# MCU_STM32_L496ZGT6.net
KiCad netlist of a schematic drawn in Altium Designer
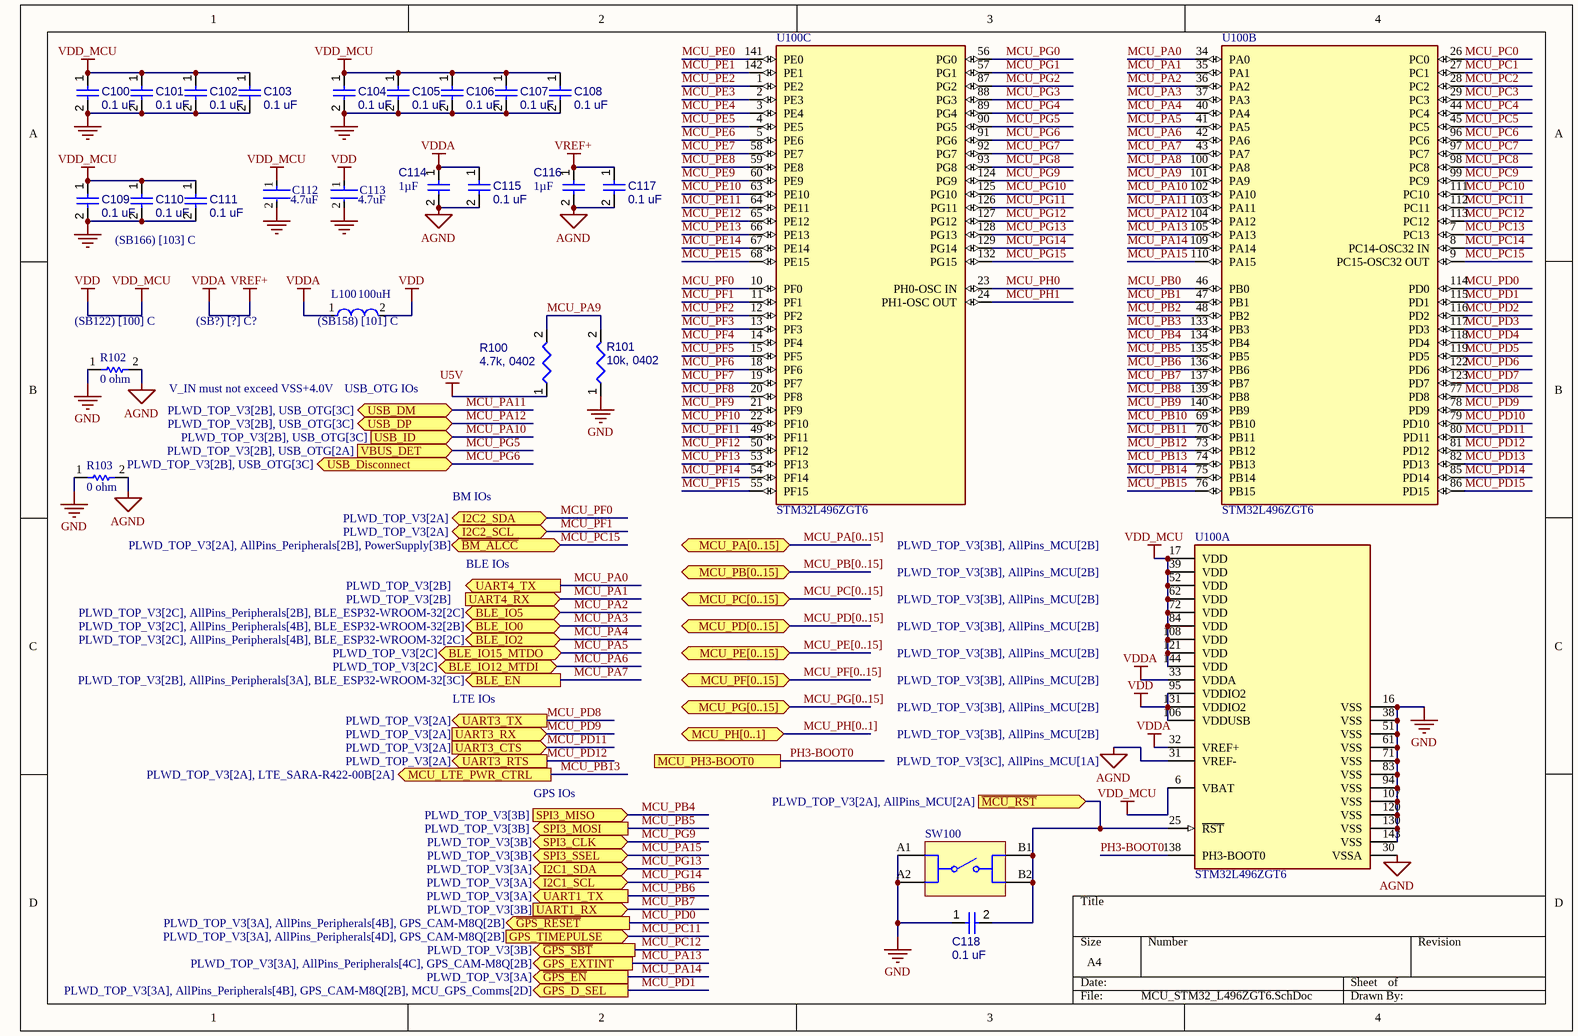
[diagram p0: MCU_STM32_L496ZGT6.SchDoc]

(export (version "E")
  (design (tool "Eeschema 10.0.6"))
  (components
    (comp (ref "C100")
      (value "0.1 uF")
      (footprint "CAPC1005X56X25LL10T15")
      (description "Chip Capacitor, 0.1 uF, +/- 5%, 16 V, 0402 (1005 Metric)")
      (fields (field (name "TOLERANCE") "5%"))
      (libsource (lib "Carleton University") (part "CAP-NP-2"))
    )
    (comp (ref "C101")
      (value "0.1 uF")
      (footprint "CAPC1005X56X25LL10T15")
      (description "Chip Capacitor, 0.1 uF, +/- 5%, 16 V, 0402 (1005 Metric)")
      (fields (field (name "TOLERANCE") "5%"))
      (libsource (lib "Carleton University") (part "CAP-NP-2"))
    )
    (comp (ref "C102")
      (value "0.1 uF")
      (footprint "CAPC1005X56X25LL10T15")
      (description "Chip Capacitor, 0.1 uF, +/- 5%, 16 V, 0402 (1005 Metric)")
      (fields (field (name "TOLERANCE") "5%"))
      (libsource (lib "Carleton University") (part "CAP-NP-2"))
    )
    (comp (ref "C103")
      (value "0.1 uF")
      (footprint "CAPC1005X56X25LL10T15")
      (description "Chip Capacitor, 0.1 uF, +/- 5%, 16 V, 0402 (1005 Metric)")
      (fields (field (name "TOLERANCE") "5%"))
      (libsource (lib "Carleton University") (part "CAP-NP-2"))
    )
    (comp (ref "C104")
      (value "0.1 uF")
      (footprint "CAPC1005X56X25LL10T15")
      (description "Chip Capacitor, 0.1 uF, +/- 5%, 16 V, 0402 (1005 Metric)")
      (fields (field (name "TOLERANCE") "5%"))
      (libsource (lib "Carleton University") (part "CAP-NP-2"))
    )
    (comp (ref "C105")
      (value "0.1 uF")
      (footprint "CAPC1005X56X25LL10T15")
      (description "Chip Capacitor, 0.1 uF, +/- 5%, 16 V, 0402 (1005 Metric)")
      (fields (field (name "TOLERANCE") "5%"))
      (libsource (lib "Carleton University") (part "CAP-NP-2"))
    )
    (comp (ref "C106")
      (value "0.1 uF")
      (footprint "CAPC1005X56X25LL10T15")
      (description "Chip Capacitor, 0.1 uF, +/- 5%, 16 V, 0402 (1005 Metric)")
      (fields (field (name "TOLERANCE") "5%"))
      (libsource (lib "Carleton University") (part "CAP-NP-2"))
    )
    (comp (ref "C107")
      (value "0.1 uF")
      (footprint "CAPC1005X56X25LL10T15")
      (description "Chip Capacitor, 0.1 uF, +/- 5%, 16 V, 0402 (1005 Metric)")
      (fields (field (name "TOLERANCE") "5%"))
      (libsource (lib "Carleton University") (part "CAP-NP-2"))
    )
    (comp (ref "C108")
      (value "0.1 uF")
      (footprint "CAPC1005X56X25LL10T15")
      (description "Chip Capacitor, 0.1 uF, +/- 5%, 16 V, 0402 (1005 Metric)")
      (fields (field (name "TOLERANCE") "5%"))
      (libsource (lib "Carleton University") (part "CAP-NP-2"))
    )
    (comp (ref "C109")
      (value "0.1 uF")
      (footprint "CAPC1005X56X25LL10T15")
      (description "Chip Capacitor, 0.1 uF, +/- 5%, 16 V, 0402 (1005 Metric)")
      (fields (field (name "TOLERANCE") "5%"))
      (libsource (lib "Carleton University") (part "CAP-NP-2"))
    )
    (comp (ref "C110")
      (value "0.1 uF")
      (footprint "CAPC1005X56X25LL10T15")
      (description "Chip Capacitor, 0.1 uF, +/- 5%, 16 V, 0402 (1005 Metric)")
      (fields (field (name "TOLERANCE") "5%"))
      (libsource (lib "Carleton University") (part "CAP-NP-2"))
    )
    (comp (ref "C111")
      (value "0.1 uF")
      (footprint "CAPC1005X56X25LL10T15")
      (description "Chip Capacitor, 0.1 uF, +/- 5%, 16 V, 0402 (1005 Metric)")
      (fields (field (name "TOLERANCE") "5%"))
      (libsource (lib "Carleton University") (part "CAP-NP-2"))
    )
    (comp (ref "C112")
      (value "CL05A475MP5NRNC")
      (footprint "FP-CL282-IPC_C")
      (description "Cap Ceramic 4.7uF 10V X5R ±20% SMD 0402 +85°C Paper T/R")
      (fields (field (name "CAPACITANCE") "4.7uF") (field (name "TOLERANCE") "20%"))
      (libsource (lib "Altium Content Vault") (part "b4654b650e69147ec39a6b967a45e02"))
    )
    (comp (ref "C113")
      (value "CL05A475MP5NRNC")
      (footprint "FP-CL282-IPC_C")
      (description "Cap Ceramic 4.7uF 10V X5R ±20% SMD 0402 +85°C Paper T/R")
      (fields (field (name "CAPACITANCE") "4.7uF") (field (name "TOLERANCE") "20%"))
      (libsource (lib "Altium Content Vault") (part "b4654b650e69147ec39a6b967a45e02"))
    )
    (comp (ref "C114")
      (value "1µF")
      (footprint "CAPC0402(1005)60_L")
      (description "Chip Capacitor, 1µF +/-20%, 10V, 0402, Thickness 0.6 mm")
      (fields (field (name "TOLERANCE") "10%") (field (name "Comment") "Capacitor 1µF +/-20% 10V 0402"))
      (libsource (lib "Carleton University") (part "CAP-NP-2"))
    )
    (comp (ref "C115")
      (value "0.1 uF")
      (footprint "CAPC1005X56X25LL10T15")
      (description "Chip Capacitor, 0.1 uF, +/- 5%, 16 V, 0402 (1005 Metric)")
      (fields (field (name "TOLERANCE") "5%"))
      (libsource (lib "Carleton University") (part "CAP-NP-2"))
    )
    (comp (ref "C116")
      (value "1µF")
      (footprint "CAPC0402(1005)60_L")
      (description "Chip Capacitor, 1µF +/-20%, 10V, 0402, Thickness 0.6 mm")
      (fields (field (name "TOLERANCE") "10%") (field (name "Comment") "Capacitor 1µF +/-20% 10V 0402"))
      (libsource (lib "Carleton University") (part "CAP-NP-2"))
    )
    (comp (ref "C117")
      (value "0.1 uF")
      (footprint "CAPC1005X56X25LL10T15")
      (description "Chip Capacitor, 0.1 uF, +/- 5%, 16 V, 0402 (1005 Metric)")
      (fields (field (name "TOLERANCE") "5%"))
      (libsource (lib "Carleton University") (part "CAP-NP-2"))
    )
    (comp (ref "C118")
      (value "0.1 uF")
      (footprint "CAPC1005X56X25LL10T15")
      (description "Chip Capacitor, 0.1 uF, +/- 5%, 16 V, 0402 (1005 Metric)")
      (fields (field (name "TOLERANCE") "5%"))
      (libsource (lib "Carleton University") (part "CAP-NP-2"))
    )
    (comp (ref "L100")
      (value "100uH")
      (footprint "FP-MLZ2012-1_25-IPC_C")
      (description "(MLZ2012N101LT000)\r\nShielded Multilayer Inductor 100uH ±20% 140mA 4550mΩ SMD 0805")
      (fields (field (name "TOLERANCE") "20%"))
      (libsource (lib "Altium Content Vault") (part "725321dda6339637d4d059423bc1c3c"))
    )
    (comp (ref "R100")
      (value "4.7k, 0402")
      (footprint "RESC0402(1005)_L")
      (description "Chip Resistor, 4,7 kOhms, +/-1 %, 63 mW, -55 to 155 degC, 0402")
      (fields (field (name "POWER") "63mW") (field (name "TOLERANCE") "1%"))
      (libsource (lib "Carleton University") (part "RES-2"))
    )
    (comp (ref "R101")
      (value "10k, 0402")
      (footprint "RESC1005X40X25ML05T05")
      (description "Chip Resistor, 10 KOhm, +/- 1%, 0.1 W, -55 to 155 degC, 0402 (1005 Metric)")
      (fields (field (name "TOLERANCE") "1%") (field (name "POWER") "100mW"))
      (libsource (lib "Carleton University") (part "RES-2"))
    )
    (comp (ref "R102")
      (value "0 ohm")
      (footprint "RESC1005X40X25LL05T10")
      (fields (field (name "MANUFACTURER") "Panasonic") (field (name "PART NUMBER") "ERJ-S020R00X"))
      (libsource (lib "Altium Content Vault") (part "RES"))
    )
    (comp (ref "R103")
      (value "0 ohm")
      (footprint "RESC1005X40X25LL05T10")
      (fields (field (name "MANUFACTURER") "Panasonic") (field (name "PART NUMBER") "ERJ-S020R00X"))
      (libsource (lib "Altium Content Vault") (part "RES"))
    )
    (comp (ref "SW100")
      (value "430182070816")
      (footprint "WS-TASV_L6W6H7_4301x20708x6")
      (libsource (lib "Altium Content Vault") (part "SPST-NO_4P"))
    )
    (comp (ref "U100")
      (value "STM32L496ZGT6")
      (footprint "FP-LQFP144-1A-MFG")
      (description "IC MCU 32BIT 1MB FLASH 144LQFP")
      (fields
        (field (name "MANUFACTURER") "STMicroelectronics")
        (field (name "OCTOPART") "https://octopart.com/stm32l496zgt6-stmicroelectronics-80927210")
      )
      (libsource (lib "Altium Content Vault") (part "f6bd984deb1ec052b3cf6fb0542fb75"))
    )
  )
  (nets
    (net (code "1") (name "/MCU_PA0") (class "Default")
      (node (ref "U100") (pin "34") (pinfunction "PA0_34") (pintype "bidirectional"))
    )
    (net (code "2") (name "/MCU_PA1") (class "Default")
      (node (ref "U100") (pin "35") (pinfunction "PA1_35") (pintype "bidirectional"))
    )
    (net (code "3") (name "/MCU_PA2") (class "Default")
      (node (ref "U100") (pin "36") (pinfunction "PA2_36") (pintype "bidirectional"))
    )
    (net (code "4") (name "/MCU_PA3") (class "Default")
      (node (ref "U100") (pin "37") (pinfunction "PA3_37") (pintype "bidirectional"))
    )
    (net (code "5") (name "/MCU_PA4") (class "Default")
      (node (ref "U100") (pin "40") (pinfunction "PA4_40") (pintype "bidirectional"))
    )
    (net (code "6") (name "/MCU_PA5") (class "Default")
      (node (ref "U100") (pin "41") (pinfunction "PA5_41") (pintype "bidirectional"))
    )
    (net (code "7") (name "/MCU_PA6") (class "Default")
      (node (ref "U100") (pin "42") (pinfunction "PA6_42") (pintype "bidirectional"))
    )
    (net (code "8") (name "/MCU_PA7") (class "Default")
      (node (ref "U100") (pin "43") (pinfunction "PA7_43") (pintype "bidirectional"))
    )
    (net (code "9") (name "/MCU_PA8") (class "Default")
      (node (ref "U100") (pin "100") (pinfunction "PA8_100") (pintype "bidirectional"))
    )
    (net (code "10") (name "/MCU_PA9") (class "Default")
      (node (ref "R100") (pin "2") (pinfunction "2_2") (pintype "passive"))
      (node (ref "R101") (pin "2") (pinfunction "2_2") (pintype "passive"))
      (node (ref "U100") (pin "101") (pinfunction "PA9_101") (pintype "bidirectional"))
    )
    (net (code "11") (name "/MCU_PA10") (class "Default")
      (node (ref "U100") (pin "102") (pinfunction "PA10_102") (pintype "bidirectional"))
    )
    (net (code "12") (name "/MCU_PA11") (class "Default")
      (node (ref "U100") (pin "103") (pinfunction "PA11_103") (pintype "bidirectional"))
    )
    (net (code "13") (name "/MCU_PA12") (class "Default")
      (node (ref "U100") (pin "104") (pinfunction "PA12_104") (pintype "bidirectional"))
    )
    (net (code "14") (name "/MCU_PA13") (class "Default")
      (node (ref "U100") (pin "105") (pinfunction "PA13_105") (pintype "bidirectional"))
    )
    (net (code "15") (name "/MCU_PA14") (class "Default")
      (node (ref "U100") (pin "109") (pinfunction "PA14_109") (pintype "bidirectional"))
    )
    (net (code "16") (name "/MCU_PA15") (class "Default")
      (node (ref "U100") (pin "110") (pinfunction "PA15_110") (pintype "bidirectional"))
    )
    (net (code "18") (name "/MCU_PB0") (class "Default")
      (node (ref "U100") (pin "46") (pinfunction "PB0_46") (pintype "bidirectional"))
    )
    (net (code "19") (name "/MCU_PB1") (class "Default")
      (node (ref "U100") (pin "47") (pinfunction "PB1_47") (pintype "bidirectional"))
    )
    (net (code "20") (name "/MCU_PB2") (class "Default")
      (node (ref "U100") (pin "48") (pinfunction "PB2_48") (pintype "bidirectional"))
    )
    (net (code "21") (name "/MCU_PB3") (class "Default")
      (node (ref "U100") (pin "133") (pinfunction "PB3_133") (pintype "bidirectional"))
    )
    (net (code "22") (name "/MCU_PB4") (class "Default")
      (node (ref "U100") (pin "134") (pinfunction "PB4_134") (pintype "bidirectional"))
    )
    (net (code "23") (name "/MCU_PB5") (class "Default")
      (node (ref "U100") (pin "135") (pinfunction "PB5_135") (pintype "bidirectional"))
    )
    (net (code "24") (name "/MCU_PB6") (class "Default")
      (node (ref "U100") (pin "136") (pinfunction "PB6_136") (pintype "bidirectional"))
    )
    (net (code "25") (name "/MCU_PB7") (class "Default")
      (node (ref "U100") (pin "137") (pinfunction "PB7_137") (pintype "bidirectional"))
    )
    (net (code "26") (name "/MCU_PB8") (class "Default")
      (node (ref "U100") (pin "139") (pinfunction "PB8_139") (pintype "bidirectional"))
    )
    (net (code "27") (name "/MCU_PB9") (class "Default")
      (node (ref "U100") (pin "140") (pinfunction "PB9_140") (pintype "bidirectional"))
    )
    (net (code "28") (name "/MCU_PB10") (class "Default")
      (node (ref "U100") (pin "69") (pinfunction "PB10_69") (pintype "bidirectional"))
    )
    (net (code "29") (name "/MCU_PB11") (class "Default")
      (node (ref "U100") (pin "70") (pinfunction "PB11_70") (pintype "bidirectional"))
    )
    (net (code "30") (name "/MCU_PB12") (class "Default")
      (node (ref "U100") (pin "73") (pinfunction "PB12_73") (pintype "bidirectional"))
    )
    (net (code "31") (name "/MCU_PB13") (class "Default")
      (node (ref "U100") (pin "74") (pinfunction "PB13_74") (pintype "bidirectional"))
    )
    (net (code "32") (name "/MCU_PB14") (class "Default")
      (node (ref "U100") (pin "75") (pinfunction "PB14_75") (pintype "bidirectional"))
    )
    (net (code "33") (name "/MCU_PB15") (class "Default")
      (node (ref "U100") (pin "76") (pinfunction "PB15_76") (pintype "bidirectional"))
    )
    (net (code "35") (name "/MCU_PC0") (class "Default")
      (node (ref "U100") (pin "26") (pinfunction "PC0_26") (pintype "bidirectional"))
    )
    (net (code "36") (name "/MCU_PC1") (class "Default")
      (node (ref "U100") (pin "27") (pinfunction "PC1_27") (pintype "bidirectional"))
    )
    (net (code "37") (name "/MCU_PC2") (class "Default")
      (node (ref "U100") (pin "28") (pinfunction "PC2_28") (pintype "bidirectional"))
    )
    (net (code "38") (name "/MCU_PC3") (class "Default")
      (node (ref "U100") (pin "29") (pinfunction "PC3_29") (pintype "bidirectional"))
    )
    (net (code "39") (name "/MCU_PC4") (class "Default")
      (node (ref "U100") (pin "44") (pinfunction "PC4_44") (pintype "bidirectional"))
    )
    (net (code "40") (name "/MCU_PC5") (class "Default")
      (node (ref "U100") (pin "45") (pinfunction "PC5_45") (pintype "bidirectional"))
    )
    (net (code "41") (name "/MCU_PC6") (class "Default")
      (node (ref "U100") (pin "96") (pinfunction "PC6_96") (pintype "bidirectional"))
    )
    (net (code "42") (name "/MCU_PC7") (class "Default")
      (node (ref "U100") (pin "97") (pinfunction "PC7_97") (pintype "bidirectional"))
    )
    (net (code "43") (name "/MCU_PC8") (class "Default")
      (node (ref "U100") (pin "98") (pinfunction "PC8_98") (pintype "bidirectional"))
    )
    (net (code "44") (name "/MCU_PC9") (class "Default")
      (node (ref "U100") (pin "99") (pinfunction "PC9_99") (pintype "bidirectional"))
    )
    (net (code "45") (name "/MCU_PC10") (class "Default")
      (node (ref "U100") (pin "111") (pinfunction "PC10_111") (pintype "bidirectional"))
    )
    (net (code "46") (name "/MCU_PC11") (class "Default")
      (node (ref "U100") (pin "112") (pinfunction "PC11_112") (pintype "bidirectional"))
    )
    (net (code "47") (name "/MCU_PC12") (class "Default")
      (node (ref "U100") (pin "113") (pinfunction "PC12_113") (pintype "bidirectional"))
    )
    (net (code "48") (name "/MCU_PC13") (class "Default")
      (node (ref "U100") (pin "7") (pinfunction "PC13_7") (pintype "bidirectional"))
    )
    (net (code "49") (name "/MCU_PC14") (class "Default")
      (node (ref "U100") (pin "8") (pinfunction "PC14-OSC32_IN_8") (pintype "bidirectional"))
    )
    (net (code "50") (name "/MCU_PC15") (class "Default")
      (node (ref "U100") (pin "9") (pinfunction "PC15-OSC32_OUT_9") (pintype "bidirectional"))
    )
    (net (code "52") (name "/MCU_PD0") (class "Default")
      (node (ref "U100") (pin "114") (pinfunction "PD0_114") (pintype "bidirectional"))
    )
    (net (code "53") (name "/MCU_PD1") (class "Default")
      (node (ref "U100") (pin "115") (pinfunction "PD1_115") (pintype "bidirectional"))
    )
    (net (code "54") (name "/MCU_PD2") (class "Default")
      (node (ref "U100") (pin "116") (pinfunction "PD2_116") (pintype "bidirectional"))
    )
    (net (code "55") (name "/MCU_PD3") (class "Default")
      (node (ref "U100") (pin "117") (pinfunction "PD3_117") (pintype "bidirectional"))
    )
    (net (code "56") (name "/MCU_PD4") (class "Default")
      (node (ref "U100") (pin "118") (pinfunction "PD4_118") (pintype "bidirectional"))
    )
    (net (code "57") (name "/MCU_PD5") (class "Default")
      (node (ref "U100") (pin "119") (pinfunction "PD5_119") (pintype "bidirectional"))
    )
    (net (code "58") (name "/MCU_PD6") (class "Default")
      (node (ref "U100") (pin "122") (pinfunction "PD6_122") (pintype "bidirectional"))
    )
    (net (code "59") (name "/MCU_PD7") (class "Default")
      (node (ref "U100") (pin "123") (pinfunction "PD7_123") (pintype "bidirectional"))
    )
    (net (code "60") (name "/MCU_PD8") (class "Default")
      (node (ref "U100") (pin "77") (pinfunction "PD8_77") (pintype "bidirectional"))
    )
    (net (code "61") (name "/MCU_PD9") (class "Default")
      (node (ref "U100") (pin "78") (pinfunction "PD9_78") (pintype "bidirectional"))
    )
    (net (code "62") (name "/MCU_PD10") (class "Default")
      (node (ref "U100") (pin "79") (pinfunction "PD10_79") (pintype "bidirectional"))
    )
    (net (code "63") (name "/MCU_PD11") (class "Default")
      (node (ref "U100") (pin "80") (pinfunction "PD11_80") (pintype "bidirectional"))
    )
    (net (code "64") (name "/MCU_PD12") (class "Default")
      (node (ref "U100") (pin "81") (pinfunction "PD12_81") (pintype "bidirectional"))
    )
    (net (code "65") (name "/MCU_PD13") (class "Default")
      (node (ref "U100") (pin "82") (pinfunction "PD13_82") (pintype "bidirectional"))
    )
    (net (code "66") (name "/MCU_PD14") (class "Default")
      (node (ref "U100") (pin "85") (pinfunction "PD14_85") (pintype "bidirectional"))
    )
    (net (code "67") (name "/MCU_PD15") (class "Default")
      (node (ref "U100") (pin "86") (pinfunction "PD15_86") (pintype "bidirectional"))
    )
    (net (code "69") (name "/MCU_PE0") (class "Default")
      (node (ref "U100") (pin "141") (pinfunction "PE0_141") (pintype "bidirectional"))
    )
    (net (code "70") (name "/MCU_PE1") (class "Default")
      (node (ref "U100") (pin "142") (pinfunction "PE1_142") (pintype "bidirectional"))
    )
    (net (code "71") (name "/MCU_PE2") (class "Default")
      (node (ref "U100") (pin "1") (pinfunction "PE2_1") (pintype "bidirectional"))
    )
    (net (code "72") (name "/MCU_PE3") (class "Default")
      (node (ref "U100") (pin "2") (pinfunction "PE3_2") (pintype "bidirectional"))
    )
    (net (code "73") (name "/MCU_PE4") (class "Default")
      (node (ref "U100") (pin "3") (pinfunction "PE4_3") (pintype "bidirectional"))
    )
    (net (code "74") (name "/MCU_PE5") (class "Default")
      (node (ref "U100") (pin "4") (pinfunction "PE5_4") (pintype "bidirectional"))
    )
    (net (code "75") (name "/MCU_PE6") (class "Default")
      (node (ref "U100") (pin "5") (pinfunction "PE6_5") (pintype "bidirectional"))
    )
    (net (code "76") (name "/MCU_PE7") (class "Default")
      (node (ref "U100") (pin "58") (pinfunction "PE7_58") (pintype "bidirectional"))
    )
    (net (code "77") (name "/MCU_PE8") (class "Default")
      (node (ref "U100") (pin "59") (pinfunction "PE8_59") (pintype "bidirectional"))
    )
    (net (code "78") (name "/MCU_PE9") (class "Default")
      (node (ref "U100") (pin "60") (pinfunction "PE9_60") (pintype "bidirectional"))
    )
    (net (code "79") (name "/MCU_PE10") (class "Default")
      (node (ref "U100") (pin "63") (pinfunction "PE10_63") (pintype "bidirectional"))
    )
    (net (code "80") (name "/MCU_PE11") (class "Default")
      (node (ref "U100") (pin "64") (pinfunction "PE11_64") (pintype "bidirectional"))
    )
    (net (code "81") (name "/MCU_PE12") (class "Default")
      (node (ref "U100") (pin "65") (pinfunction "PE12_65") (pintype "bidirectional"))
    )
    (net (code "82") (name "/MCU_PE13") (class "Default")
      (node (ref "U100") (pin "66") (pinfunction "PE13_66") (pintype "bidirectional"))
    )
    (net (code "83") (name "/MCU_PE14") (class "Default")
      (node (ref "U100") (pin "67") (pinfunction "PE14_67") (pintype "bidirectional"))
    )
    (net (code "84") (name "/MCU_PE15") (class "Default")
      (node (ref "U100") (pin "68") (pinfunction "PE15_68") (pintype "bidirectional"))
    )
    (net (code "86") (name "/MCU_PF0") (class "Default")
      (node (ref "U100") (pin "10") (pinfunction "PF0_10") (pintype "bidirectional"))
    )
    (net (code "87") (name "/MCU_PF1") (class "Default")
      (node (ref "U100") (pin "11") (pinfunction "PF1_11") (pintype "bidirectional"))
    )
    (net (code "88") (name "/MCU_PF2") (class "Default")
      (node (ref "U100") (pin "12") (pinfunction "PF2_12") (pintype "bidirectional"))
    )
    (net (code "89") (name "/MCU_PF3") (class "Default")
      (node (ref "U100") (pin "13") (pinfunction "PF3_13") (pintype "bidirectional"))
    )
    (net (code "90") (name "/MCU_PF4") (class "Default")
      (node (ref "U100") (pin "14") (pinfunction "PF4_14") (pintype "bidirectional"))
    )
    (net (code "91") (name "/MCU_PF5") (class "Default")
      (node (ref "U100") (pin "15") (pinfunction "PF5_15") (pintype "bidirectional"))
    )
    (net (code "92") (name "/MCU_PF6") (class "Default")
      (node (ref "U100") (pin "18") (pinfunction "PF6_18") (pintype "bidirectional"))
    )
    (net (code "93") (name "/MCU_PF7") (class "Default")
      (node (ref "U100") (pin "19") (pinfunction "PF7_19") (pintype "bidirectional"))
    )
    (net (code "94") (name "/MCU_PF8") (class "Default")
      (node (ref "U100") (pin "20") (pinfunction "PF8_20") (pintype "bidirectional"))
    )
    (net (code "95") (name "/MCU_PF9") (class "Default")
      (node (ref "U100") (pin "21") (pinfunction "PF9_21") (pintype "bidirectional"))
    )
    (net (code "96") (name "/MCU_PF10") (class "Default")
      (node (ref "U100") (pin "22") (pinfunction "PF10_22") (pintype "bidirectional"))
    )
    (net (code "97") (name "/MCU_PF11") (class "Default")
      (node (ref "U100") (pin "49") (pinfunction "PF11_49") (pintype "bidirectional"))
    )
    (net (code "98") (name "/MCU_PF12") (class "Default")
      (node (ref "U100") (pin "50") (pinfunction "PF12_50") (pintype "bidirectional"))
    )
    (net (code "99") (name "/MCU_PF13") (class "Default")
      (node (ref "U100") (pin "53") (pinfunction "PF13_53") (pintype "bidirectional"))
    )
    (net (code "100") (name "/MCU_PF14") (class "Default")
      (node (ref "U100") (pin "54") (pinfunction "PF14_54") (pintype "bidirectional"))
    )
    (net (code "101") (name "/MCU_PF15") (class "Default")
      (node (ref "U100") (pin "55") (pinfunction "PF15_55") (pintype "bidirectional"))
    )
    (net (code "103") (name "/MCU_PG0") (class "Default")
      (node (ref "U100") (pin "56") (pinfunction "PG0_56") (pintype "bidirectional"))
    )
    (net (code "104") (name "/MCU_PG1") (class "Default")
      (node (ref "U100") (pin "57") (pinfunction "PG1_57") (pintype "bidirectional"))
    )
    (net (code "105") (name "/MCU_PG2") (class "Default")
      (node (ref "U100") (pin "87") (pinfunction "PG2_87") (pintype "bidirectional"))
    )
    (net (code "106") (name "/MCU_PG3") (class "Default")
      (node (ref "U100") (pin "88") (pinfunction "PG3_88") (pintype "bidirectional"))
    )
    (net (code "107") (name "/MCU_PG4") (class "Default")
      (node (ref "U100") (pin "89") (pinfunction "PG4_89") (pintype "bidirectional"))
    )
    (net (code "108") (name "/MCU_PG5") (class "Default")
      (node (ref "U100") (pin "90") (pinfunction "PG5_90") (pintype "bidirectional"))
    )
    (net (code "109") (name "/MCU_PG6") (class "Default")
      (node (ref "U100") (pin "91") (pinfunction "PG6_91") (pintype "bidirectional"))
    )
    (net (code "110") (name "/MCU_PG7") (class "Default")
      (node (ref "U100") (pin "92") (pinfunction "PG7_92") (pintype "bidirectional"))
    )
    (net (code "111") (name "/MCU_PG8") (class "Default")
      (node (ref "U100") (pin "93") (pinfunction "PG8_93") (pintype "bidirectional"))
    )
    (net (code "112") (name "/MCU_PG9") (class "Default")
      (node (ref "U100") (pin "124") (pinfunction "PG9_124") (pintype "bidirectional"))
    )
    (net (code "113") (name "/MCU_PG10") (class "Default")
      (node (ref "U100") (pin "125") (pinfunction "PG10_125") (pintype "bidirectional"))
    )
    (net (code "114") (name "/MCU_PG11") (class "Default")
      (node (ref "U100") (pin "126") (pinfunction "PG11_126") (pintype "bidirectional"))
    )
    (net (code "115") (name "/MCU_PG12") (class "Default")
      (node (ref "U100") (pin "127") (pinfunction "PG12_127") (pintype "bidirectional"))
    )
    (net (code "116") (name "/MCU_PG13") (class "Default")
      (node (ref "U100") (pin "128") (pinfunction "PG13_128") (pintype "bidirectional"))
    )
    (net (code "117") (name "/MCU_PG14") (class "Default")
      (node (ref "U100") (pin "129") (pinfunction "PG14_129") (pintype "bidirectional"))
    )
    (net (code "118") (name "/MCU_PG15") (class "Default")
      (node (ref "U100") (pin "132") (pinfunction "PG15_132") (pintype "bidirectional"))
    )
    (net (code "120") (name "/MCU_PH0") (class "Default")
      (node (ref "U100") (pin "23") (pinfunction "PH0-OSC_IN_23") (pintype "bidirectional"))
    )
    (net (code "121") (name "/MCU_PH1") (class "Default")
      (node (ref "U100") (pin "24") (pinfunction "PH1-OSC_OUT_24") (pintype "bidirectional"))
    )
    (net (code "123") (name "/PH3-BOOT0") (class "Default")
      (node (ref "U100") (pin "138") (pinfunction "PH3-BOOT0_138") (pintype "passive"))
    )
    (net (code "124") (name "/~{MCU_RST}") (class "Default")
      (node (ref "C118") (pin "2") (pinfunction "2_2") (pintype "passive"))
      (node (ref "SW100") (pin "B1") (pinfunction "B1_B1") (pintype "passive"))
      (node (ref "SW100") (pin "B2") (pinfunction "B2_B2") (pintype "passive"))
      (node (ref "U100") (pin "25") (pinfunction "~{RST}_25") (pintype "input"))
    )
    (net (code "125") (name "AGND") (class "Default")
      (node (ref "C114") (pin "2") (pinfunction "2_2") (pintype "passive"))
      (node (ref "C115") (pin "2") (pinfunction "2_2") (pintype "passive"))
      (node (ref "C116") (pin "2") (pinfunction "2_2") (pintype "passive"))
      (node (ref "C117") (pin "2") (pinfunction "2_2") (pintype "passive"))
      (node (ref "R102") (pin "2") (pinfunction "2_2") (pintype "passive"))
      (node (ref "R103") (pin "2") (pinfunction "2_2") (pintype "passive"))
      (node (ref "U100") (pin "30") (pinfunction "VSSA_30") (pintype "power_in"))
      (node (ref "U100") (pin "31") (pinfunction "VREF-_31") (pintype "power_in"))
    )
    (net (code "126") (name "GND") (class "Default")
      (node (ref "C100") (pin "2") (pinfunction "2_2") (pintype "passive"))
      (node (ref "C101") (pin "2") (pinfunction "2_2") (pintype "passive"))
      (node (ref "C102") (pin "2") (pinfunction "2_2") (pintype "passive"))
      (node (ref "C103") (pin "2") (pinfunction "2_2") (pintype "passive"))
      (node (ref "C104") (pin "2") (pinfunction "2_2") (pintype "passive"))
      (node (ref "C105") (pin "2") (pinfunction "2_2") (pintype "passive"))
      (node (ref "C106") (pin "2") (pinfunction "2_2") (pintype "passive"))
      (node (ref "C107") (pin "2") (pinfunction "2_2") (pintype "passive"))
      (node (ref "C108") (pin "2") (pinfunction "2_2") (pintype "passive"))
      (node (ref "C109") (pin "2") (pinfunction "2_2") (pintype "passive"))
      (node (ref "C110") (pin "2") (pinfunction "2_2") (pintype "passive"))
      (node (ref "C111") (pin "2") (pinfunction "2_2") (pintype "passive"))
      (node (ref "C112") (pin "2") (pinfunction "2_2") (pintype "passive"))
      (node (ref "C113") (pin "2") (pinfunction "2_2") (pintype "passive"))
      (node (ref "C118") (pin "1") (pinfunction "1_1") (pintype "passive"))
      (node (ref "R101") (pin "1") (pinfunction "1_1") (pintype "passive"))
      (node (ref "R102") (pin "1") (pinfunction "1_1") (pintype "passive"))
      (node (ref "R103") (pin "1") (pinfunction "1_1") (pintype "passive"))
      (node (ref "SW100") (pin "A1") (pinfunction "A1_A1") (pintype "passive"))
      (node (ref "SW100") (pin "A2") (pinfunction "A2_A2") (pintype "passive"))
      (node (ref "U100") (pin "107") (pinfunction "VSS_107") (pintype "power_in"))
      (node (ref "U100") (pin "120") (pinfunction "VSS_120") (pintype "power_in"))
      (node (ref "U100") (pin "130") (pinfunction "VSS_130") (pintype "power_in"))
      (node (ref "U100") (pin "143") (pinfunction "VSS_143") (pintype "power_in"))
      (node (ref "U100") (pin "16") (pinfunction "VSS_16") (pintype "power_in"))
      (node (ref "U100") (pin "38") (pinfunction "VSS_38") (pintype "power_in"))
      (node (ref "U100") (pin "51") (pinfunction "VSS_51") (pintype "power_in"))
      (node (ref "U100") (pin "61") (pinfunction "VSS_61") (pintype "power_in"))
      (node (ref "U100") (pin "71") (pinfunction "VSS_71") (pintype "power_in"))
      (node (ref "U100") (pin "83") (pinfunction "VSS_83") (pintype "power_in"))
      (node (ref "U100") (pin "94") (pinfunction "VSS_94") (pintype "power_in"))
    )
    (net (code "127") (name "U5V") (class "Default")
      (node (ref "R100") (pin "1") (pinfunction "1_1") (pintype "passive"))
    )
    (net (code "128") (name "VDD") (class "Default")
      (node (ref "C100") (pin "1") (pinfunction "1_1") (pintype "passive"))
      (node (ref "C101") (pin "1") (pinfunction "1_1") (pintype "passive"))
      (node (ref "C102") (pin "1") (pinfunction "1_1") (pintype "passive"))
      (node (ref "C103") (pin "1") (pinfunction "1_1") (pintype "passive"))
      (node (ref "C104") (pin "1") (pinfunction "1_1") (pintype "passive"))
      (node (ref "C105") (pin "1") (pinfunction "1_1") (pintype "passive"))
      (node (ref "C106") (pin "1") (pinfunction "1_1") (pintype "passive"))
      (node (ref "C107") (pin "1") (pinfunction "1_1") (pintype "passive"))
      (node (ref "C108") (pin "1") (pinfunction "1_1") (pintype "passive"))
      (node (ref "C109") (pin "1") (pinfunction "1_1") (pintype "passive"))
      (node (ref "C110") (pin "1") (pinfunction "1_1") (pintype "passive"))
      (node (ref "C111") (pin "1") (pinfunction "1_1") (pintype "passive"))
      (node (ref "C112") (pin "1") (pinfunction "1_1") (pintype "passive"))
      (node (ref "C113") (pin "1") (pinfunction "1_1") (pintype "passive"))
      (node (ref "L100") (pin "2") (pinfunction "2_2") (pintype "passive"))
      (node (ref "U100") (pin "106") (pinfunction "VDDUSB_106") (pintype "power_in"))
      (node (ref "U100") (pin "108") (pinfunction "VDD_108") (pintype "power_in"))
      (node (ref "U100") (pin "121") (pinfunction "VDD_121") (pintype "power_in"))
      (node (ref "U100") (pin "131") (pinfunction "VDDIO2_131") (pintype "power_in"))
      (node (ref "U100") (pin "144") (pinfunction "VDD_144") (pintype "power_in"))
      (node (ref "U100") (pin "17") (pinfunction "VDD_17") (pintype "power_in"))
      (node (ref "U100") (pin "39") (pinfunction "VDD_39") (pintype "power_in"))
      (node (ref "U100") (pin "52") (pinfunction "VDD_52") (pintype "power_in"))
      (node (ref "U100") (pin "6") (pinfunction "VBAT_6") (pintype "power_in"))
      (node (ref "U100") (pin "62") (pinfunction "VDD_62") (pintype "power_in"))
      (node (ref "U100") (pin "72") (pinfunction "VDD_72") (pintype "power_in"))
      (node (ref "U100") (pin "84") (pinfunction "VDD_84") (pintype "power_in"))
      (node (ref "U100") (pin "95") (pinfunction "VDDIO2_95") (pintype "power_in"))
    )
    (net (code "129") (name "VDDA") (class "Default")
      (node (ref "C114") (pin "1") (pinfunction "1_1") (pintype "passive"))
      (node (ref "C115") (pin "1") (pinfunction "1_1") (pintype "passive"))
      (node (ref "C116") (pin "1") (pinfunction "1_1") (pintype "passive"))
      (node (ref "C117") (pin "1") (pinfunction "1_1") (pintype "passive"))
      (node (ref "L100") (pin "1") (pinfunction "1_1") (pintype "passive"))
      (node (ref "U100") (pin "32") (pinfunction "VREF+_32") (pintype "power_in"))
      (node (ref "U100") (pin "33") (pinfunction "VDDA_33") (pintype "power_in"))
    )
  )
)
